# P11_ETH1_RMII.net
KiCad netlist of a schematic drawn in Altium Designer
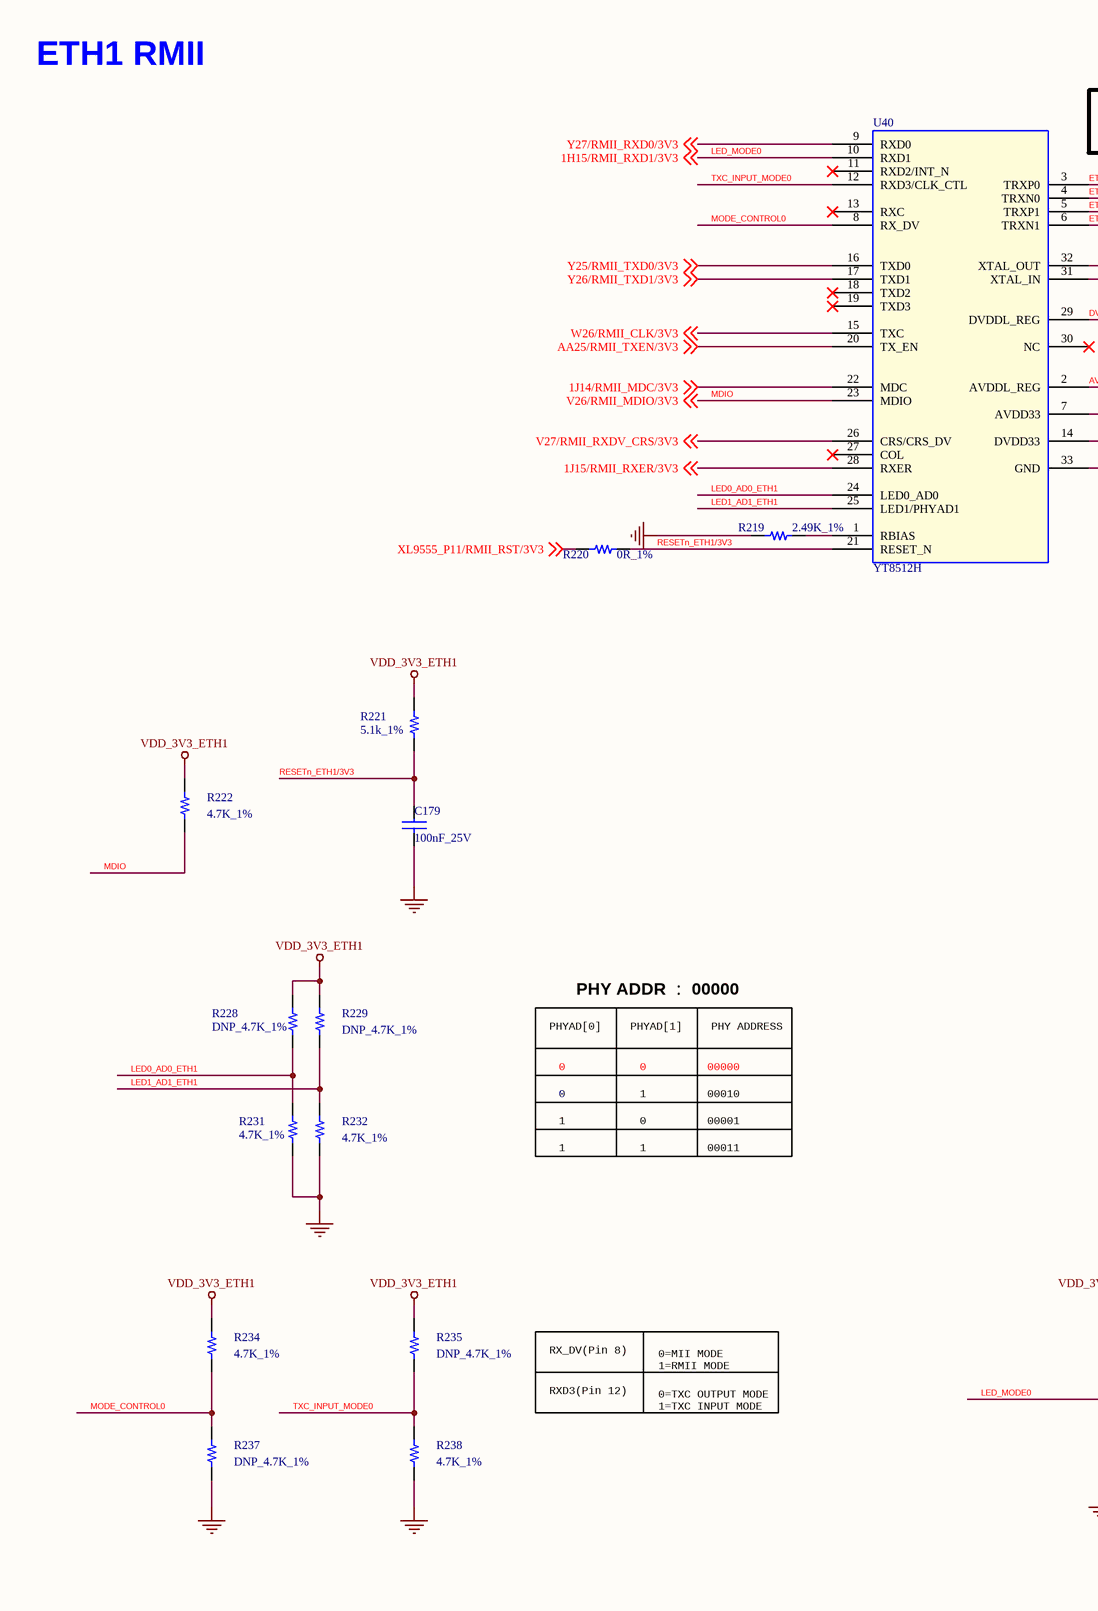
[diagram p0: P11_ETH1 RMII.SchDoc, left]
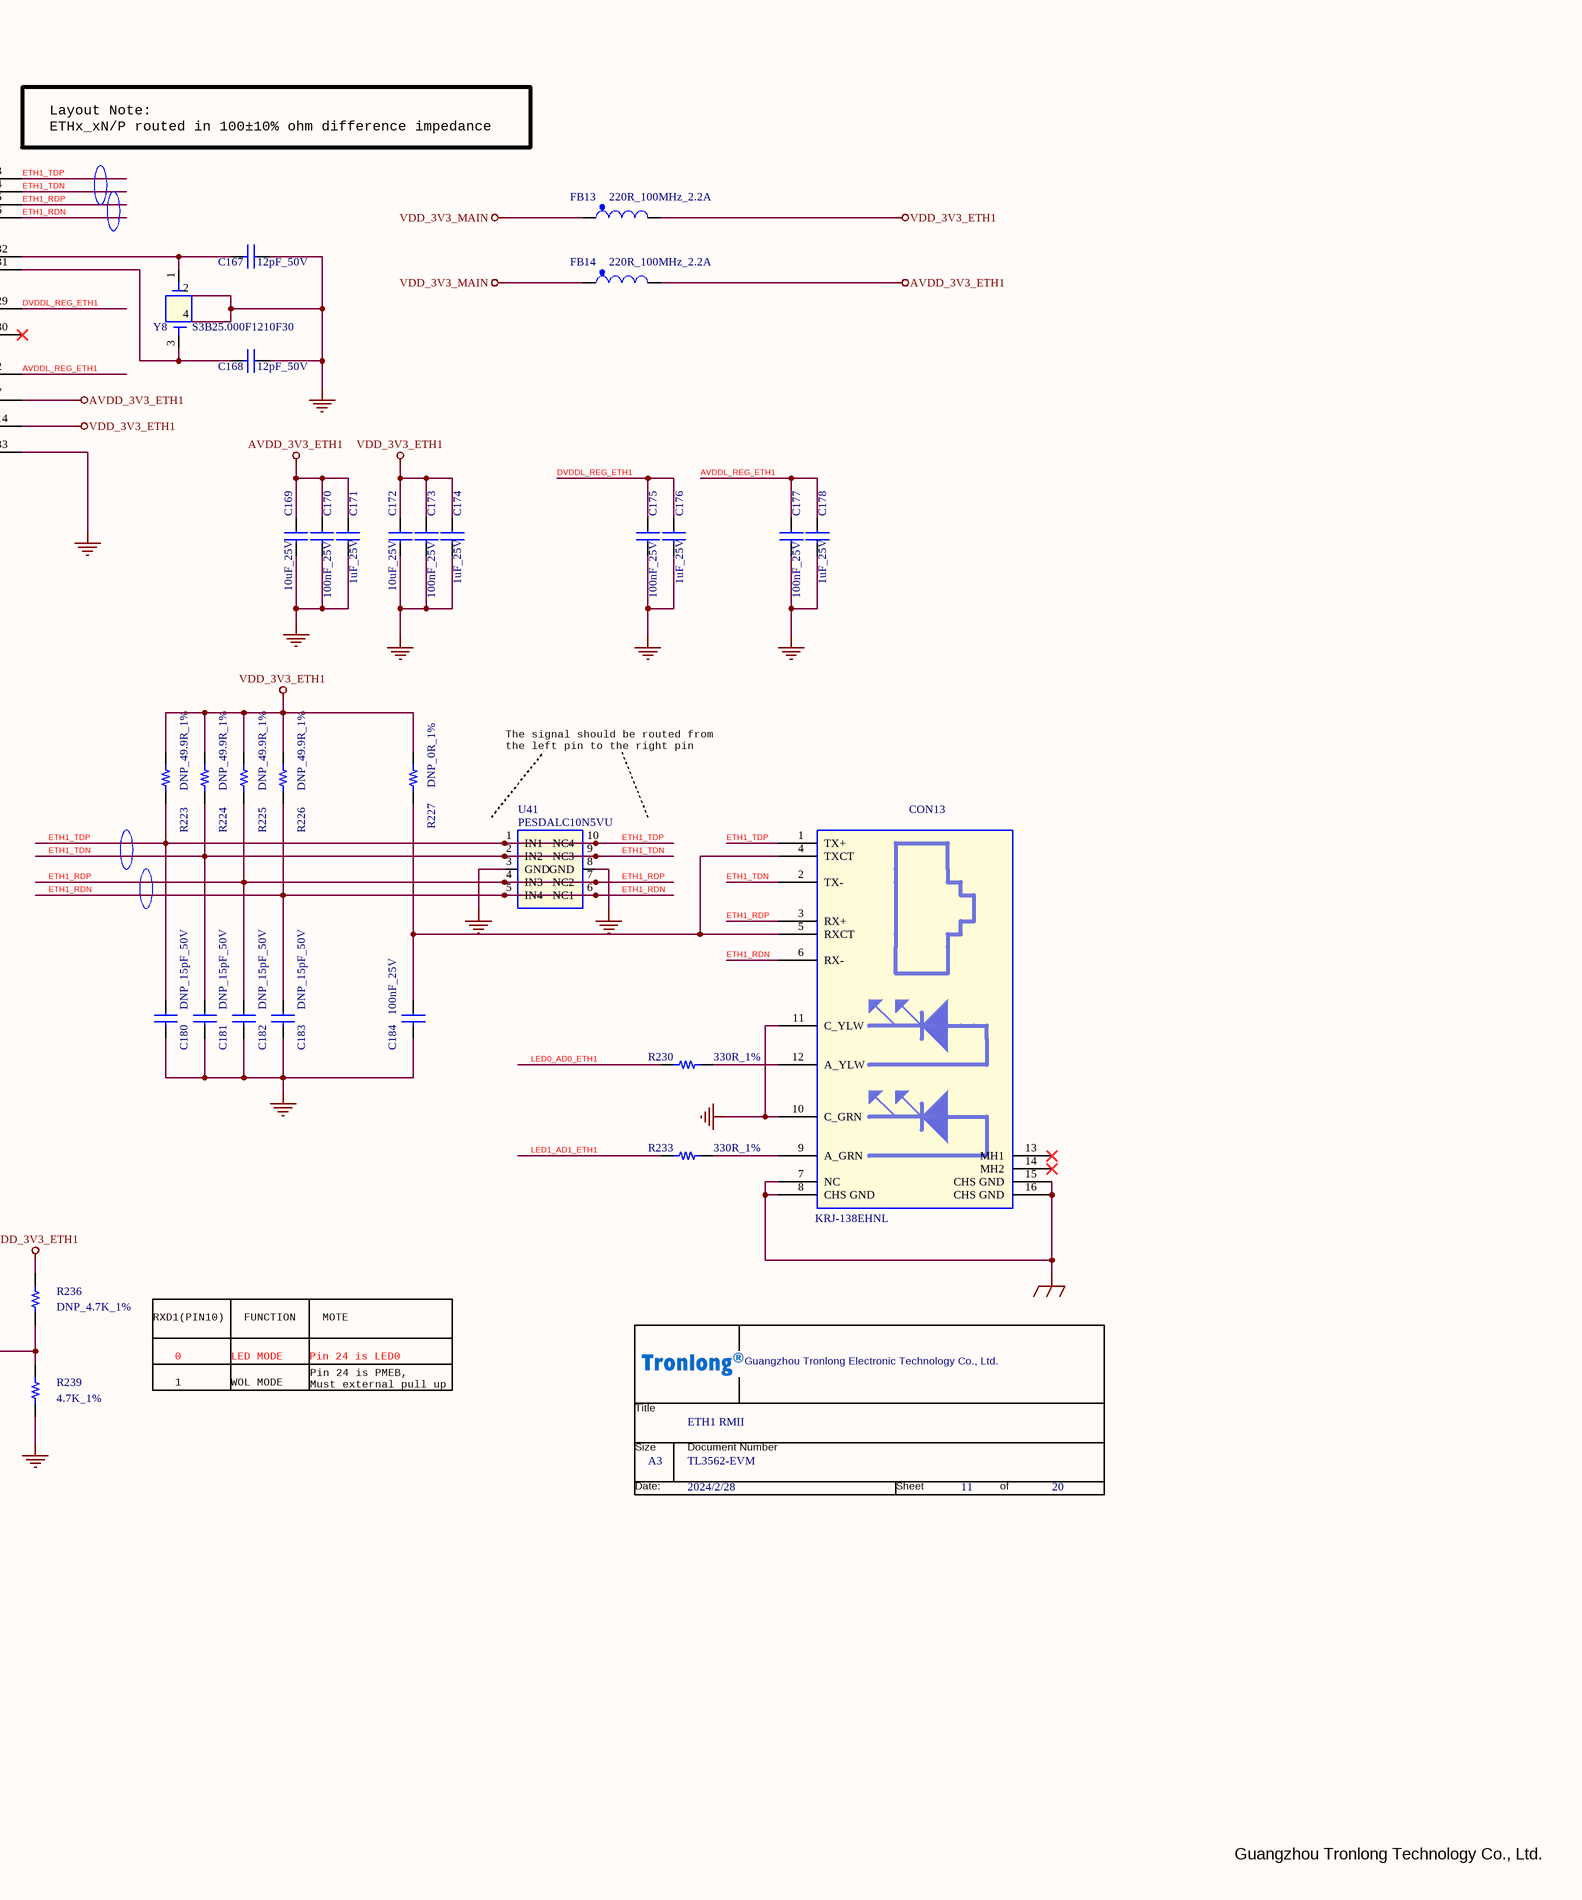
[diagram p1: P11_ETH1 RMII.SchDoc, right]

(export (version "E")
  (design (tool "Eeschema 10.0.6"))
  (components
    (comp (ref "C167")
      (value "12pF_50V")
      (footprint "C0402")
      (description "贴片陶瓷电容,12pF,5%,50V,COG")
      (libsource (lib "*") (part "CAP NP_2"))
    )
    (comp (ref "C168")
      (value "12pF_50V")
      (footprint "C0402")
      (description "贴片陶瓷电容,12pF,5%,50V,COG")
      (libsource (lib "*") (part "CAP NP_2"))
    )
    (comp (ref "C169")
      (value "10uF_25V")
      (footprint "C0603")
      (description "贴片陶瓷电容,10uF,10%,10V,X5R")
      (libsource (lib "*") (part "CAP NP_2"))
    )
    (comp (ref "C170")
      (value "100nF_25V")
      (footprint "C0402")
      (description "贴片陶瓷电容,100nF,10%,25V,X5R")
      (libsource (lib "*") (part "CAP NP_2"))
    )
    (comp (ref "C171")
      (value "1uF_25V")
      (footprint "C0603")
      (description "贴片陶瓷电容,1uF,10%,25V,X5R")
      (libsource (lib "*") (part "CAP NP_2"))
    )
    (comp (ref "C172")
      (value "10uF_25V")
      (footprint "C0603")
      (description "贴片陶瓷电容,10uF,10%,10V,X5R")
      (libsource (lib "*") (part "CAP NP_2"))
    )
    (comp (ref "C173")
      (value "100nF_25V")
      (footprint "C0402")
      (description "贴片陶瓷电容,100nF,10%,25V,X5R")
      (libsource (lib "*") (part "CAP NP_2"))
    )
    (comp (ref "C174")
      (value "1uF_25V")
      (footprint "C0603")
      (description "贴片陶瓷电容,1uF,10%,25V,X5R")
      (libsource (lib "*") (part "CAP NP_2"))
    )
    (comp (ref "C175")
      (value "100nF_25V")
      (footprint "C0402")
      (description "贴片陶瓷电容,100nF,10%,25V,X5R")
      (libsource (lib "*") (part "CAP NP_2"))
    )
    (comp (ref "C176")
      (value "1uF_25V")
      (footprint "C0603")
      (description "贴片陶瓷电容,1uF,10%,25V,X5R")
      (libsource (lib "*") (part "CAP NP_2"))
    )
    (comp (ref "C177")
      (value "100nF_25V")
      (footprint "C0402")
      (description "贴片陶瓷电容,100nF,10%,25V,X5R")
      (libsource (lib "*") (part "CAP NP_2"))
    )
    (comp (ref "C178")
      (value "1uF_25V")
      (footprint "C0603")
      (description "贴片陶瓷电容,1uF,10%,25V,X5R")
      (libsource (lib "*") (part "CAP NP_2"))
    )
    (comp (ref "C179")
      (value "100nF_25V")
      (footprint "C0402")
      (description "贴片陶瓷电容,100nF,10%,25V,X5R")
      (libsource (lib "*") (part "CAP NP_2"))
    )
    (comp (ref "C180")
      (value "DNP_15pF_50V")
      (footprint "C0603")
      (description "贴片陶瓷电容,15pF,5%,50V,COG")
      (libsource (lib "*") (part "CAP NP_3"))
    )
    (comp (ref "C181")
      (value "DNP_15pF_50V")
      (footprint "C0603")
      (description "贴片陶瓷电容,15pF,5%,50V,COG")
      (libsource (lib "*") (part "CAP NP_3"))
    )
    (comp (ref "C182")
      (value "DNP_15pF_50V")
      (footprint "C0603")
      (description "贴片陶瓷电容,15pF,5%,50V,COG")
      (libsource (lib "*") (part "CAP NP_3"))
    )
    (comp (ref "C183")
      (value "DNP_15pF_50V")
      (footprint "C0603")
      (description "贴片陶瓷电容,15pF,5%,50V,COG")
      (libsource (lib "*") (part "CAP NP_3"))
    )
    (comp (ref "C184")
      (value "100nF_25V")
      (footprint "C0402")
      (description "贴片陶瓷电容,100nF,10%,25V,X5R")
      (libsource (lib "*") (part "CAP NP_3"))
    )
    (comp (ref "CON13")
      (value "KRJ-138EHNL")
      (footprint "CON_YDS_13F-64GYD2PLXNL")
      (description "RJ45连接器,12PIN,90度,母座,插件")
      (fields (field (name "MANUFACTURER") "东莞市科优达电子科技有限公司（DGKYD）"))
      (libsource (lib "*") (part "ETHERNET CONNECTER"))
    )
    (comp (ref "FB13")
      (value "220R_100MHz_2.2A")
      (footprint "L0603")
      (description "磁珠,50mΩ,2.2A,220R@100MHz")
      (fields
        (field (name "MANUFACTURER PARTNUMBER") "UPZ1608U221-2R2TF")
        (field (name "MANUFACTURER") "深圳顺络电子股份有限公司（Sunlord）")
      )
      (libsource (lib "*") (part "FERRITE BEAD_Dup2"))
    )
    (comp (ref "FB14")
      (value "220R_100MHz_2.2A")
      (footprint "L0603")
      (description "磁珠,50mΩ,2.2A,220R@100MHz")
      (fields
        (field (name "MANUFACTURER") "深圳顺络电子股份有限公司（Sunlord）")
        (field (name "MANUFACTURER PARTNUMBER") "UPZ1608U221-2R2TF")
      )
      (libsource (lib "*") (part "FERRITE BEAD_Dup2"))
    )
    (comp (ref "R219")
      (value "2.49K_1%")
      (footprint "R0603")
      (description "贴片电阻,2.49K,±1%,1/10W")
      (libsource (lib "*") (part "R_1"))
    )
    (comp (ref "R220")
      (value "0R_1%")
      (footprint "R0402")
      (description "0R,±1%,R0402,≥1/16W")
      (libsource (lib "*") (part "R_1"))
    )
    (comp (ref "R221")
      (value "5.1k_1%")
      (footprint "R0402")
      (description "贴片电阻,5.1K,±1%,1/16W")
      (libsource (lib "*") (part "R 1%"))
    )
    (comp (ref "R222")
      (value "4.7K_1%")
      (footprint "R0402")
      (description "贴片电阻,4.7K,±1%,1/16W")
      (libsource (lib "*") (part "R_1"))
    )
    (comp (ref "R223")
      (value "DNP_49.9R_1%")
      (footprint "R0603")
      (description "贴片电阻,49.9R,±1%,1/10W")
      (libsource (lib "*") (part "R_0"))
    )
    (comp (ref "R224")
      (value "DNP_49.9R_1%")
      (footprint "R0603")
      (description "贴片电阻,49.9R,±1%,1/10W")
      (libsource (lib "*") (part "R_0"))
    )
    (comp (ref "R225")
      (value "DNP_49.9R_1%")
      (footprint "R0603")
      (description "贴片电阻,49.9R,±1%,1/10W")
      (libsource (lib "*") (part "R_0"))
    )
    (comp (ref "R226")
      (value "DNP_49.9R_1%")
      (footprint "R0603")
      (description "贴片电阻,49.9R,±1%,1/10W")
      (libsource (lib "*") (part "R_0"))
    )
    (comp (ref "R227")
      (value "DNP_0R_1%")
      (footprint "R0402")
      (description "贴片电阻,0R,±1%,1/16W")
      (libsource (lib "*") (part "R_0"))
    )
    (comp (ref "R228")
      (value "DNP_4.7K_1%")
      (footprint "R0402")
      (description "贴片电阻,4.7K,±1%,1/16W")
      (libsource (lib "*") (part "R_1"))
    )
    (comp (ref "R229")
      (value "DNP_4.7K_1%")
      (footprint "R0402")
      (description "贴片电阻,4.7K,±1%,1/16W")
      (libsource (lib "*") (part "R_1"))
    )
    (comp (ref "R230")
      (value "330R_1%")
      (footprint "R0402")
      (description "贴片电阻,330R,±1%,1/16W")
      (libsource (lib "*") (part "R_0"))
    )
    (comp (ref "R231")
      (value "4.7K_1%")
      (footprint "R0402")
      (description "贴片电阻,4.7K,±1%,1/16W")
      (libsource (lib "*") (part "R_1"))
    )
    (comp (ref "R232")
      (value "4.7K_1%")
      (footprint "R0402")
      (description "贴片电阻,4.7K,±1%,1/16W")
      (libsource (lib "*") (part "R_1"))
    )
    (comp (ref "R233")
      (value "330R_1%")
      (footprint "R0402")
      (description "贴片电阻,330R,±1%,1/16W")
      (libsource (lib "*") (part "R_0"))
    )
    (comp (ref "R234")
      (value "4.7K_1%")
      (footprint "R0402")
      (description "贴片电阻,4.7K,±1%,1/16W")
      (libsource (lib "*") (part "R_1"))
    )
    (comp (ref "R235")
      (value "DNP_4.7K_1%")
      (footprint "R0402")
      (description "贴片电阻,4.7K,±1%,1/16W")
      (libsource (lib "*") (part "R_1"))
    )
    (comp (ref "R236")
      (value "DNP_4.7K_1%")
      (footprint "R0402")
      (description "贴片电阻,4.7K,±1%,1/16W")
      (libsource (lib "*") (part "R_1"))
    )
    (comp (ref "R237")
      (value "DNP_4.7K_1%")
      (footprint "R0402")
      (description "贴片电阻,4.7K,±1%,1/16W")
      (libsource (lib "*") (part "R_1"))
    )
    (comp (ref "R238")
      (value "4.7K_1%")
      (footprint "R0402")
      (description "贴片电阻,4.7K,±1%,1/16W")
      (libsource (lib "*") (part "R_1"))
    )
    (comp (ref "R239")
      (value "4.7K_1%")
      (footprint "R0402")
      (description "贴片电阻,4.7K,±1%,1/16W")
      (libsource (lib "*") (part "R_1"))
    )
    (comp (ref "U40")
      (value "YT8512H")
      (footprint "QFN32")
      (description "以太网收发器，MII/RMII")
      (fields (field (name "MANUFACTURER") "苏州裕太微电子有限公司（Motorcomm）"))
      (libsource (lib "*") (part "YT8512H_1"))
    )
    (comp (ref "U41")
      (value "PESDALC10N5VU")
      (footprint "DFN-10-2510")
      (description "4通道超低电容瞬态抑制器")
      (fields (field (name "MANUFACTURER") "上海芯导电子科技有限公司（Prisemi）"))
      (libsource (lib "*") (part "SU099PGTR"))
    )
    (comp (ref "Y8")
      (value "S3B25.000F1210F30")
      (footprint "SMD_3225")
      (description "四脚无源晶振,25MHz,±10ppm,12pF,30Ω,±30ppm")
      (fields (field (name "MANUFACTURER") "深圳市星通时频电子有限公司公司（JSCJ）"))
      (libsource (lib "*") (part "CRYSTAL-4 PIN"))
    )
  )
  (nets
    (net (code "1") (name "/AVDDL_REG_ETH1") (class "Default")
      (node (ref "C177") (pin "1") (pinfunction "1_1") (pintype "passive"))
      (node (ref "C178") (pin "1") (pinfunction "1_1") (pintype "passive"))
      (node (ref "U40") (pin "2") (pinfunction "AVDDL_REG_2") (pintype "passive"))
    )
    (net (code "2") (name "/DVDDL_REG_ETH1") (class "Default")
      (node (ref "C175") (pin "1") (pinfunction "1_1") (pintype "passive"))
      (node (ref "C176") (pin "1") (pinfunction "1_1") (pintype "passive"))
      (node (ref "U40") (pin "29") (pinfunction "DVDDL_REG_29") (pintype "passive"))
    )
    (net (code "3") (name "/ETH1_RDN") (class "Default")
      (node (ref "C183") (pin "1") (pinfunction "1_1") (pintype "passive"))
      (node (ref "CON13") (pin "6") (pinfunction "RX-_6") (pintype "passive"))
      (node (ref "R226") (pin "2") (pinfunction "2_2") (pintype "passive"))
      (node (ref "U40") (pin "6") (pinfunction "TRXN1_6") (pintype "passive"))
      (node (ref "U41") (pin "5") (pinfunction "IN4_5") (pintype "passive"))
      (node (ref "U41") (pin "6") (pinfunction "NC1_6") (pintype "passive"))
    )
    (net (code "4") (name "/ETH1_RDP") (class "Default")
      (node (ref "C182") (pin "1") (pinfunction "1_1") (pintype "passive"))
      (node (ref "CON13") (pin "3") (pinfunction "RX+_3") (pintype "passive"))
      (node (ref "R225") (pin "2") (pinfunction "2_2") (pintype "passive"))
      (node (ref "U40") (pin "5") (pinfunction "TRXP1_5") (pintype "passive"))
      (node (ref "U41") (pin "4") (pinfunction "IN3_4") (pintype "passive"))
      (node (ref "U41") (pin "7") (pinfunction "NC2_7") (pintype "passive"))
    )
    (net (code "5") (name "/ETH1_TDN") (class "Default")
      (node (ref "C181") (pin "1") (pinfunction "1_1") (pintype "passive"))
      (node (ref "CON13") (pin "2") (pinfunction "TX-_2") (pintype "passive"))
      (node (ref "R224") (pin "2") (pinfunction "2_2") (pintype "passive"))
      (node (ref "U40") (pin "4") (pinfunction "TRXN0_4") (pintype "passive"))
      (node (ref "U41") (pin "2") (pinfunction "IN2_2") (pintype "passive"))
      (node (ref "U41") (pin "9") (pinfunction "NC3_9") (pintype "passive"))
    )
    (net (code "6") (name "/ETH1_TDP") (class "Default")
      (node (ref "C180") (pin "1") (pinfunction "1_1") (pintype "passive"))
      (node (ref "CON13") (pin "1") (pinfunction "TX+_1") (pintype "passive"))
      (node (ref "R223") (pin "2") (pinfunction "2_2") (pintype "passive"))
      (node (ref "U40") (pin "3") (pinfunction "TRXP0_3") (pintype "passive"))
      (node (ref "U41") (pin "1") (pinfunction "IN1_1") (pintype "passive"))
      (node (ref "U41") (pin "10") (pinfunction "NC4_10") (pintype "passive"))
    )
    (net (code "7") (name "/LED0_AD0_ETH1") (class "Default")
      (node (ref "R228") (pin "1") (pinfunction "1_1") (pintype "passive"))
      (node (ref "R230") (pin "1") (pinfunction "1_1") (pintype "passive"))
      (node (ref "R231") (pin "2") (pinfunction "2_2") (pintype "passive"))
      (node (ref "U40") (pin "24") (pinfunction "LED0_AD0_24") (pintype "passive"))
    )
    (net (code "8") (name "/LED1_AD1_ETH1") (class "Default")
      (node (ref "R229") (pin "1") (pinfunction "1_1") (pintype "passive"))
      (node (ref "R232") (pin "2") (pinfunction "2_2") (pintype "passive"))
      (node (ref "R233") (pin "1") (pinfunction "1_1") (pintype "passive"))
      (node (ref "U40") (pin "25") (pinfunction "LED1/PHYAD1_25") (pintype "passive"))
    )
    (net (code "9") (name "/MODE_CONTROL0") (class "Default")
      (node (ref "R234") (pin "1") (pinfunction "1_1") (pintype "passive"))
      (node (ref "R237") (pin "1") (pinfunction "1_1") (pintype "passive"))
      (node (ref "U40") (pin "8") (pinfunction "RX_DV_8") (pintype "passive"))
    )
    (net (code "10") (name "/RESETn_ETH1{slash}3V3") (class "Default")
      (node (ref "C179") (pin "1") (pinfunction "1_1") (pintype "passive"))
      (node (ref "R220") (pin "2") (pinfunction "2_2") (pintype "passive"))
      (node (ref "R221") (pin "2") (pinfunction "2_2") (pintype "passive"))
      (node (ref "U40") (pin "21") (pinfunction "RESET_N_21") (pintype "passive"))
    )
    (net (code "11") (name "/TXC_INPUT_MODE0") (class "Default")
      (node (ref "R235") (pin "1") (pinfunction "1_1") (pintype "passive"))
      (node (ref "R238") (pin "1") (pinfunction "1_1") (pintype "passive"))
      (node (ref "U40") (pin "12") (pinfunction "RXD3/CLK_CTL_12") (pintype "passive"))
    )
    (net (code "12") (name "1H15{slash}RMII_RXD1{slash}3V3") (class "Default")
      (node (ref "R236") (pin "1") (pinfunction "1_1") (pintype "passive"))
      (node (ref "R239") (pin "1") (pinfunction "1_1") (pintype "passive"))
      (node (ref "U40") (pin "10") (pinfunction "RXD1_10") (pintype "passive"))
    )
    (net (code "13") (name "1J14{slash}RMII_MDC{slash}3V3") (class "Default")
      (node (ref "U40") (pin "22") (pinfunction "MDC_22") (pintype "passive"))
    )
    (net (code "14") (name "1J15{slash}RMII_RXER{slash}3V3") (class "Default")
      (node (ref "U40") (pin "28") (pinfunction "RXER_28") (pintype "passive"))
    )
    (net (code "15") (name "AA25{slash}RMII_TXEN{slash}3V3") (class "Default")
      (node (ref "U40") (pin "20") (pinfunction "TX_EN_20") (pintype "passive"))
    )
    (net (code "16") (name "AVDD_3V3_ETH1") (class "Default")
      (node (ref "C169") (pin "1") (pinfunction "1_1") (pintype "passive"))
      (node (ref "C170") (pin "1") (pinfunction "1_1") (pintype "passive"))
      (node (ref "C171") (pin "1") (pinfunction "1_1") (pintype "passive"))
      (node (ref "FB14") (pin "2") (pinfunction "2_2") (pintype "passive"))
      (node (ref "U40") (pin "7") (pinfunction "AVDD33_7") (pintype "passive"))
    )
    (net (code "17") (name "EGND") (class "Default")
      (node (ref "CON13") (pin "15") (pinfunction "CHS_GND_15") (pintype "power_in"))
      (node (ref "CON13") (pin "16") (pinfunction "CHS_GND_16") (pintype "power_in"))
      (node (ref "CON13") (pin "7") (pinfunction "NC_7") (pintype "passive"))
      (node (ref "CON13") (pin "8") (pinfunction "CHS_GND_8") (pintype "power_in"))
    )
    (net (code "18") (name "GND") (class "Default")
      (node (ref "C167") (pin "1") (pinfunction "1_1") (pintype "passive"))
      (node (ref "C168") (pin "1") (pinfunction "1_1") (pintype "passive"))
      (node (ref "C169") (pin "2") (pinfunction "2_2") (pintype "passive"))
      (node (ref "C170") (pin "2") (pinfunction "2_2") (pintype "passive"))
      (node (ref "C171") (pin "2") (pinfunction "2_2") (pintype "passive"))
      (node (ref "C172") (pin "2") (pinfunction "2_2") (pintype "passive"))
      (node (ref "C173") (pin "2") (pinfunction "2_2") (pintype "passive"))
      (node (ref "C174") (pin "2") (pinfunction "2_2") (pintype "passive"))
      (node (ref "C175") (pin "2") (pinfunction "2_2") (pintype "passive"))
      (node (ref "C176") (pin "2") (pinfunction "2_2") (pintype "passive"))
      (node (ref "C177") (pin "2") (pinfunction "2_2") (pintype "passive"))
      (node (ref "C178") (pin "2") (pinfunction "2_2") (pintype "passive"))
      (node (ref "C179") (pin "2") (pinfunction "2_2") (pintype "passive"))
      (node (ref "C180") (pin "2") (pinfunction "2_2") (pintype "passive"))
      (node (ref "C181") (pin "2") (pinfunction "2_2") (pintype "passive"))
      (node (ref "C182") (pin "2") (pinfunction "2_2") (pintype "passive"))
      (node (ref "C183") (pin "2") (pinfunction "2_2") (pintype "passive"))
      (node (ref "C184") (pin "2") (pinfunction "2_2") (pintype "passive"))
      (node (ref "CON13") (pin "10") (pinfunction "C_GRN_10") (pintype "passive"))
      (node (ref "CON13") (pin "11") (pinfunction "C_YLW_11") (pintype "passive"))
      (node (ref "R219") (pin "2") (pinfunction "2_2") (pintype "passive"))
      (node (ref "R231") (pin "1") (pinfunction "1_1") (pintype "passive"))
      (node (ref "R232") (pin "1") (pinfunction "1_1") (pintype "passive"))
      (node (ref "R237") (pin "2") (pinfunction "2_2") (pintype "passive"))
      (node (ref "R238") (pin "2") (pinfunction "2_2") (pintype "passive"))
      (node (ref "R239") (pin "2") (pinfunction "2_2") (pintype "passive"))
      (node (ref "U40") (pin "33") (pinfunction "GND_33") (pintype "passive"))
      (node (ref "U41") (pin "3") (pinfunction "GND_3") (pintype "power_in"))
      (node (ref "U41") (pin "8") (pinfunction "GND_8") (pintype "power_in"))
      (node (ref "Y8") (pin "2") (pinfunction "2_2") (pintype "passive"))
      (node (ref "Y8") (pin "4") (pinfunction "4_4") (pintype "passive"))
    )
    (net (code "19") (name "Net-(CON13-A_GRN)") (class "Default")
      (node (ref "CON13") (pin "9") (pinfunction "A_GRN_9") (pintype "passive"))
      (node (ref "R233") (pin "2") (pinfunction "2_2") (pintype "passive"))
    )
    (net (code "20") (name "Net-(CON13-A_YLW)") (class "Default")
      (node (ref "CON13") (pin "12") (pinfunction "A_YLW_12") (pintype "passive"))
      (node (ref "R230") (pin "2") (pinfunction "2_2") (pintype "passive"))
    )
    (net (code "21") (name "Net-(CON13-RXCT)") (class "Default")
      (node (ref "C184") (pin "1") (pinfunction "1_1") (pintype "passive"))
      (node (ref "CON13") (pin "4") (pinfunction "TXCT_4") (pintype "passive"))
      (node (ref "CON13") (pin "5") (pinfunction "RXCT_5") (pintype "passive"))
      (node (ref "R227") (pin "1") (pinfunction "1_1") (pintype "passive"))
    )
    (net (code "22") (name "Net-(U40-RBIAS)") (class "Default")
      (node (ref "R219") (pin "1") (pinfunction "1_1") (pintype "passive"))
      (node (ref "U40") (pin "1") (pinfunction "RBIAS_1") (pintype "passive"))
    )
    (net (code "23") (name "Net-(U40-XTAL_IN)") (class "Default")
      (node (ref "C168") (pin "2") (pinfunction "2_2") (pintype "passive"))
      (node (ref "U40") (pin "31") (pinfunction "XTAL_IN_31") (pintype "passive"))
      (node (ref "Y8") (pin "3") (pinfunction "3_3") (pintype "passive"))
    )
    (net (code "24") (name "Net-(U40-XTAL_OUT)") (class "Default")
      (node (ref "C167") (pin "2") (pinfunction "2_2") (pintype "passive"))
      (node (ref "U40") (pin "32") (pinfunction "XTAL_OUT_32") (pintype "passive"))
      (node (ref "Y8") (pin "1") (pinfunction "1_1") (pintype "passive"))
    )
    (net (code "25") (name "V26{slash}RMII_MDIO{slash}3V3") (class "Default")
      (node (ref "R222") (pin "2") (pinfunction "2_2") (pintype "passive"))
      (node (ref "U40") (pin "23") (pinfunction "MDIO_23") (pintype "passive"))
    )
    (net (code "26") (name "V27{slash}RMII_RXDV_CRS{slash}3V3") (class "Default")
      (node (ref "U40") (pin "26") (pinfunction "CRS/CRS_DV_26") (pintype "passive"))
    )
    (net (code "27") (name "VDD_3V3_ETH1") (class "Default")
      (node (ref "C172") (pin "1") (pinfunction "1_1") (pintype "passive"))
      (node (ref "C173") (pin "1") (pinfunction "1_1") (pintype "passive"))
      (node (ref "C174") (pin "1") (pinfunction "1_1") (pintype "passive"))
      (node (ref "FB13") (pin "2") (pinfunction "2_2") (pintype "passive"))
      (node (ref "R221") (pin "1") (pinfunction "1_1") (pintype "passive"))
      (node (ref "R222") (pin "1") (pinfunction "1_1") (pintype "passive"))
      (node (ref "R223") (pin "1") (pinfunction "1_1") (pintype "passive"))
      (node (ref "R224") (pin "1") (pinfunction "1_1") (pintype "passive"))
      (node (ref "R225") (pin "1") (pinfunction "1_1") (pintype "passive"))
      (node (ref "R226") (pin "1") (pinfunction "1_1") (pintype "passive"))
      (node (ref "R227") (pin "2") (pinfunction "2_2") (pintype "passive"))
      (node (ref "R228") (pin "2") (pinfunction "2_2") (pintype "passive"))
      (node (ref "R229") (pin "2") (pinfunction "2_2") (pintype "passive"))
      (node (ref "R234") (pin "2") (pinfunction "2_2") (pintype "passive"))
      (node (ref "R235") (pin "2") (pinfunction "2_2") (pintype "passive"))
      (node (ref "R236") (pin "2") (pinfunction "2_2") (pintype "passive"))
      (node (ref "U40") (pin "14") (pinfunction "DVDD33_14") (pintype "passive"))
    )
    (net (code "28") (name "VDD_3V3_MAIN") (class "Default")
      (node (ref "FB13") (pin "1") (pinfunction "1_1") (pintype "passive"))
      (node (ref "FB14") (pin "1") (pinfunction "1_1") (pintype "passive"))
    )
    (net (code "29") (name "W26{slash}RMII_CLK{slash}3V3") (class "Default")
      (node (ref "U40") (pin "15") (pinfunction "TXC_15") (pintype "passive"))
    )
    (net (code "30") (name "XL9555_P11{slash}RMII_RST{slash}3V3") (class "Default")
      (node (ref "R220") (pin "1") (pinfunction "1_1") (pintype "passive"))
    )
    (net (code "31") (name "Y25{slash}RMII_TXD0{slash}3V3") (class "Default")
      (node (ref "U40") (pin "16") (pinfunction "TXD0_16") (pintype "passive"))
    )
    (net (code "32") (name "Y26{slash}RMII_TXD1{slash}3V3") (class "Default")
      (node (ref "U40") (pin "17") (pinfunction "TXD1_17") (pintype "passive"))
    )
    (net (code "33") (name "Y27{slash}RMII_RXD0{slash}3V3") (class "Default")
      (node (ref "U40") (pin "9") (pinfunction "RXD0_9") (pintype "passive"))
    )
    (net (code "34") (name "unconnected-(CON13-MH1-Pad13)") (class "Default")
      (node (ref "CON13") (pin "13") (pinfunction "MH1_13") (pintype "passive+no_connect"))
    )
    (net (code "35") (name "unconnected-(CON13-MH2-Pad14)") (class "Default")
      (node (ref "CON13") (pin "14") (pinfunction "MH2_14") (pintype "passive+no_connect"))
    )
    (net (code "36") (name "unconnected-(U40-COL-Pad27)") (class "Default")
      (node (ref "U40") (pin "27") (pinfunction "COL_27") (pintype "passive+no_connect"))
    )
    (net (code "37") (name "unconnected-(U40-NC-Pad30)") (class "Default")
      (node (ref "U40") (pin "30") (pinfunction "NC_30") (pintype "passive+no_connect"))
    )
    (net (code "38") (name "unconnected-(U40-RXC-Pad13)") (class "Default")
      (node (ref "U40") (pin "13") (pinfunction "RXC_13") (pintype "passive+no_connect"))
    )
    (net (code "39") (name "unconnected-(U40-RXD2{slash}INT_N-Pad11)") (class "Default")
      (node (ref "U40") (pin "11") (pinfunction "RXD2/INT_N_11") (pintype "passive+no_connect"))
    )
    (net (code "40") (name "unconnected-(U40-TXD2-Pad18)") (class "Default")
      (node (ref "U40") (pin "18") (pinfunction "TXD2_18") (pintype "passive+no_connect"))
    )
    (net (code "41") (name "unconnected-(U40-TXD3-Pad19)") (class "Default")
      (node (ref "U40") (pin "19") (pinfunction "TXD3_19") (pintype "passive+no_connect"))
    )
  )
)
